# team_throttle_control_draft_2.net
KiCad netlist of a schematic drawn in EAGLE
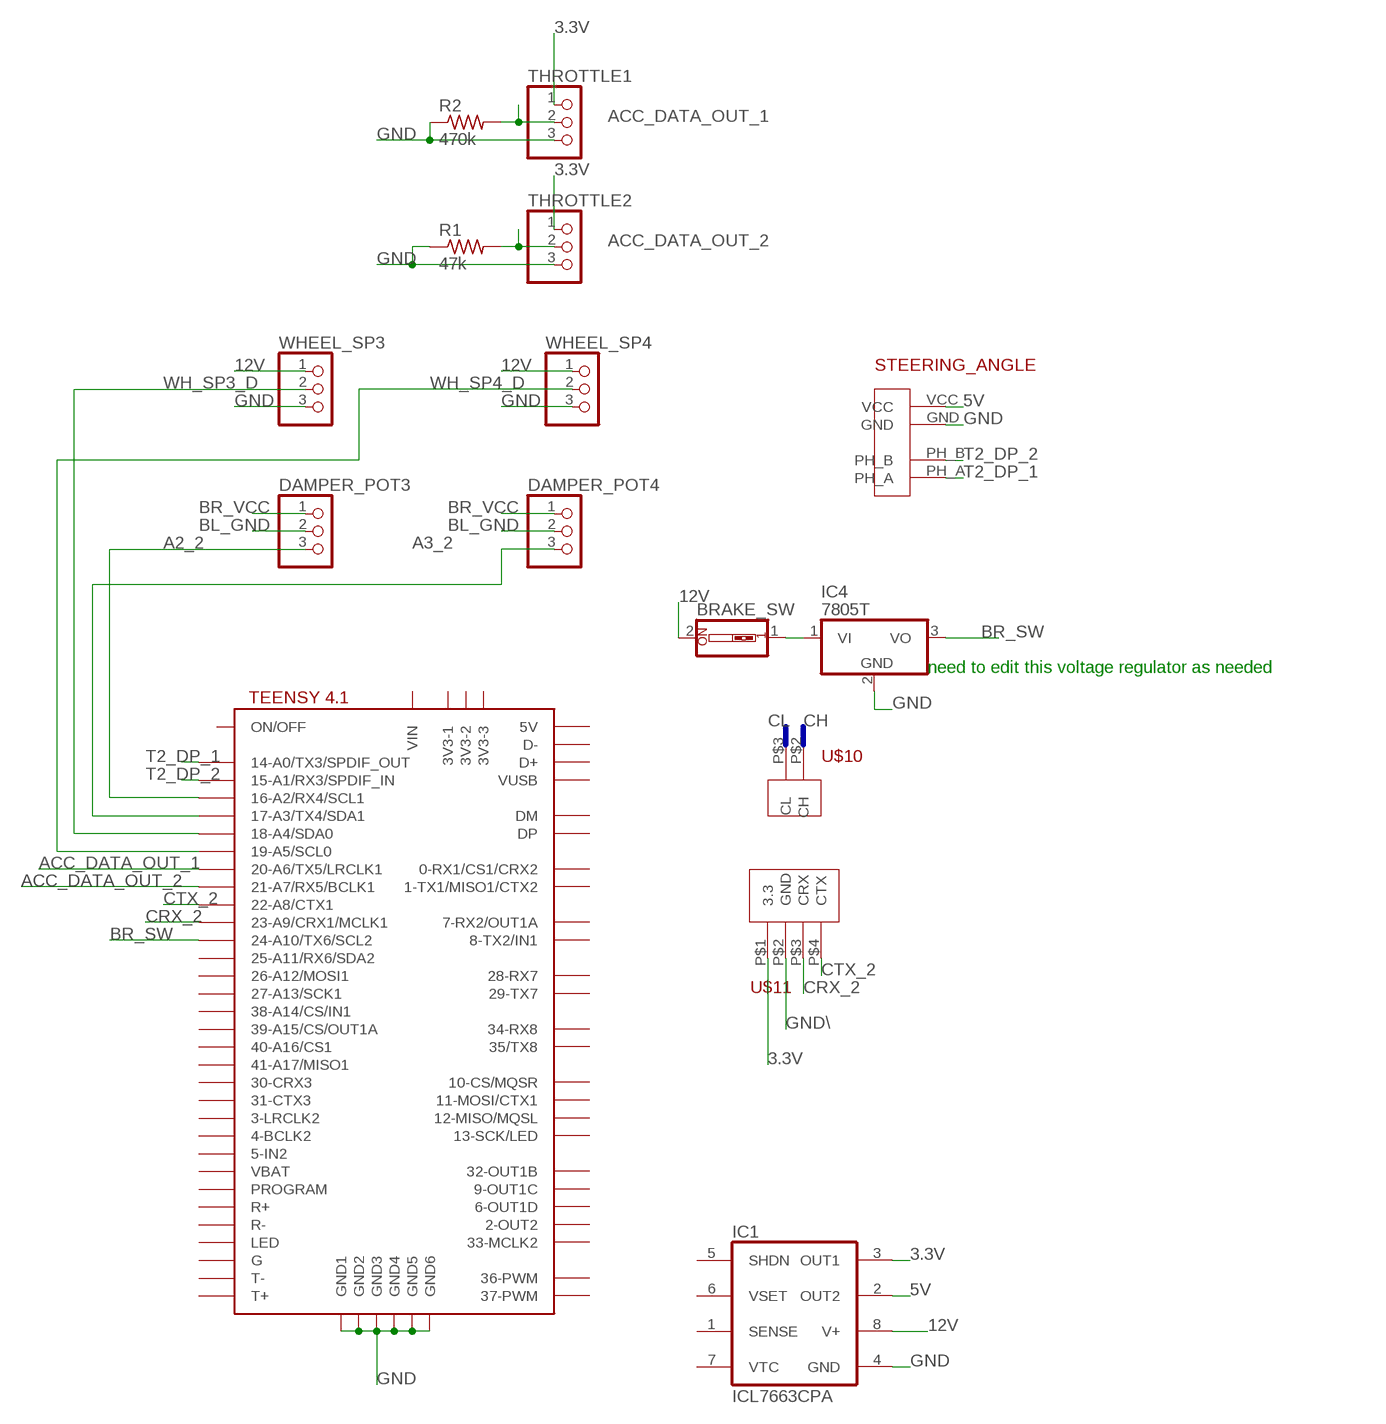
[diagram p0: schematic, sheet 1]

(export (version "E")
  (design (tool "Eeschema 10.0.6"))
  (components
    (comp (ref "BRAKE_SW")
      (value "SW_DIP-1")
      (footprint "eagle-import:EDG-01")
      (libsource (lib "eagle-import") (part "SW_DIP-1"))
    )
    (comp (ref "DAMPER_POT3")
      (value "PINHD-1X3CB")
      (footprint "eagle-import:1X03-CLEANBIG")
      (libsource (lib "eagle-import") (part "PINHD-1X3CB"))
    )
    (comp (ref "DAMPER_POT4")
      (value "PINHD-1X3CB")
      (footprint "eagle-import:1X03-CLEANBIG")
      (libsource (lib "eagle-import") (part "PINHD-1X3CB"))
    )
    (comp (ref "IC1")
      (value "ICL7663CPA")
      (footprint "eagle-import:DIL08")
      (libsource (lib "eagle-import") (part "ICL7663CPA"))
    )
    (comp (ref "IC4")
      (value "7805T")
      (footprint "eagle-import:TO220H")
      (libsource (lib "eagle-import") (part "78T05"))
    )
    (comp (ref "R1")
      (value "47k")
      (footprint "eagle-import:0204_7")
      (libsource (lib "eagle-import") (part "R-US_0204/7"))
    )
    (comp (ref "R2")
      (value "470k")
      (footprint "eagle-import:0204_7")
      (libsource (lib "eagle-import") (part "R-US_0204/7"))
    )
    (comp (ref "STEERING_ANGLE")
      (value "ROTARY_ENCODER")
      (footprint "eagle-import:ROTARY_ENCODER")
      (libsource (lib "eagle-import") (part "ROTARY_ENCODER"))
    )
    (comp (ref "THROTTLE1")
      (value "PINHD-1X3")
      (footprint "eagle-import:1X03")
      (libsource (lib "eagle-import") (part "PINHD-1X3"))
    )
    (comp (ref "THROTTLE2")
      (value "PINHD-1X3")
      (footprint "eagle-import:1X03")
      (libsource (lib "eagle-import") (part "PINHD-1X3"))
    )
    (comp (ref "U$3")
      (value "TEENSY41")
      (footprint "eagle-import:TEENSY41")
      (libsource (lib "eagle-import") (part "TEENSY41"))
    )
    (comp (ref "U$10")
      (value "CAN_BUS")
      (footprint "eagle-import:CAN_BUS")
      (libsource (lib "eagle-import") (part "CAN_BUS"))
    )
    (comp (ref "U$11")
      (value "CAN_TEE")
      (footprint "eagle-import:CAN_TEN")
      (libsource (lib "eagle-import") (part "CAN_TEE"))
    )
    (comp (ref "WHEEL_SP3")
      (value "PINHD-1X3")
      (footprint "eagle-import:1X03")
      (libsource (lib "eagle-import") (part "PINHD-1X3"))
    )
    (comp (ref "WHEEL_SP4")
      (value "PINHD-1X3")
      (footprint "eagle-import:1X03")
      (libsource (lib "eagle-import") (part "PINHD-1X3"))
    )
  )
  (nets
    (net (code "3") (name "/3.3V") (class "Default")
      (node (ref "IC1") (pin "3") (pinfunction "OUT1_3") (pintype "output"))
      (node (ref "THROTTLE1") (pin "1") (pinfunction "1_1") (pintype "passive"))
      (node (ref "THROTTLE2") (pin "1") (pinfunction "1_1") (pintype "passive"))
      (node (ref "U$11") (pin "P$1") (pinfunction "3.3_P$1") (pintype "bidirectional"))
    )
    (net (code "4") (name "/5V") (class "Default")
      (node (ref "IC1") (pin "2") (pinfunction "OUT2_2") (pintype "output"))
      (node (ref "STEERING_ANGLE") (pin "VCC") (pinfunction "VCC_VCC") (pintype "bidirectional"))
    )
    (net (code "5") (name "/12V") (class "Default")
      (node (ref "BRAKE_SW") (pin "2") (pinfunction "2_2") (pintype "passive"))
      (node (ref "IC1") (pin "8") (pinfunction "V+_8") (pintype "power_in"))
      (node (ref "WHEEL_SP3") (pin "1") (pinfunction "1_1") (pintype "passive"))
      (node (ref "WHEEL_SP4") (pin "1") (pinfunction "1_1") (pintype "passive"))
    )
    (net (code "6") (name "/A2_2") (class "Default")
      (node (ref "DAMPER_POT3") (pin "3") (pinfunction "3_3") (pintype "passive"))
      (node (ref "U$3") (pin "16-A2/RX4/SCL1") (pinfunction "16-A2/RX4/SCL1_16-A2/RX4/SCL1") (pintype "bidirectional"))
    )
    (net (code "7") (name "/A3_2") (class "Default")
      (node (ref "DAMPER_POT4") (pin "3") (pinfunction "3_3") (pintype "passive"))
      (node (ref "U$3") (pin "17-A3/TX4/SDA1") (pinfunction "17-A3/TX4/SDA1_17-A3/TX4/SDA1") (pintype "bidirectional"))
    )
    (net (code "8") (name "/ACC_DATA_OUT_1") (class "Default")
      (node (ref "R2") (pin "2") (pinfunction "2_2") (pintype "passive"))
      (node (ref "THROTTLE1") (pin "2") (pinfunction "2_2") (pintype "passive"))
      (node (ref "U$3") (pin "20-A6/TX5/LRCLK1") (pinfunction "20-A6/TX5/LRCLK1_20-A6/TX5/LRCLK1") (pintype "bidirectional"))
    )
    (net (code "9") (name "/ACC_DATA_OUT_2") (class "Default")
      (node (ref "R1") (pin "2") (pinfunction "2_2") (pintype "passive"))
      (node (ref "THROTTLE2") (pin "2") (pinfunction "2_2") (pintype "passive"))
      (node (ref "U$3") (pin "21-A7/RX5/BCLK1") (pinfunction "21-A7/RX5/BCLK1_21-A7/RX5/BCLK1") (pintype "bidirectional"))
    )
    (net (code "10") (name "/BL_GND") (class "Default")
      (node (ref "DAMPER_POT3") (pin "2") (pinfunction "2_2") (pintype "passive"))
      (node (ref "DAMPER_POT4") (pin "2") (pinfunction "2_2") (pintype "passive"))
    )
    (net (code "11") (name "/BR_SW") (class "Default")
      (node (ref "IC4") (pin "3") (pinfunction "VO_3") (pintype "passive"))
      (node (ref "U$3") (pin "24-A10/TX6/SCL2") (pinfunction "24-A10/TX6/SCL2_24-A10/TX6/SCL2") (pintype "bidirectional"))
    )
    (net (code "12") (name "/BR_VCC") (class "Default")
      (node (ref "DAMPER_POT3") (pin "1") (pinfunction "1_1") (pintype "passive"))
      (node (ref "DAMPER_POT4") (pin "1") (pinfunction "1_1") (pintype "passive"))
    )
    (net (code "13") (name "/CRX_2") (class "Default")
      (node (ref "U$11") (pin "P$3") (pinfunction "CRX_P$3") (pintype "bidirectional"))
      (node (ref "U$3") (pin "23-A9/CRX1/MCLK1") (pinfunction "23-A9/CRX1/MCLK1_23-A9/CRX1/MCLK1") (pintype "bidirectional"))
    )
    (net (code "14") (name "/CTX_2") (class "Default")
      (node (ref "U$11") (pin "P$4") (pinfunction "CTX_P$4") (pintype "bidirectional"))
      (node (ref "U$3") (pin "22-A8/CTX1") (pinfunction "22-A8/CTX1_22-A8/CTX1") (pintype "bidirectional"))
    )
    (net (code "15") (name "/GND") (class "Default")
      (node (ref "IC1") (pin "4") (pinfunction "GND_4") (pintype "power_in"))
      (node (ref "IC4") (pin "2") (pinfunction "GND_2") (pintype "passive"))
      (node (ref "R1") (pin "1") (pinfunction "1_1") (pintype "passive"))
      (node (ref "R2") (pin "1") (pinfunction "1_1") (pintype "passive"))
      (node (ref "STEERING_ANGLE") (pin "GND") (pinfunction "GND_GND") (pintype "bidirectional"))
      (node (ref "THROTTLE1") (pin "3") (pinfunction "3_3") (pintype "passive"))
      (node (ref "THROTTLE2") (pin "3") (pinfunction "3_3") (pintype "passive"))
      (node (ref "U$3") (pin "GND1") (pinfunction "GND1_GND1") (pintype "bidirectional"))
      (node (ref "U$3") (pin "GND2") (pinfunction "GND2_GND2") (pintype "bidirectional"))
      (node (ref "U$3") (pin "GND3") (pinfunction "GND3_GND3") (pintype "bidirectional"))
      (node (ref "U$3") (pin "GND4") (pinfunction "GND4_GND4") (pintype "bidirectional"))
      (node (ref "U$3") (pin "GND5") (pinfunction "GND5_GND5") (pintype "bidirectional"))
      (node (ref "U$3") (pin "GND6") (pinfunction "GND6_GND6") (pintype "bidirectional"))
      (node (ref "WHEEL_SP3") (pin "3") (pinfunction "3_3") (pintype "passive"))
      (node (ref "WHEEL_SP4") (pin "3") (pinfunction "3_3") (pintype "passive"))
    )
    (net (code "16") (name "/GND\\") (class "Default")
      (node (ref "U$11") (pin "P$2") (pinfunction "GND_P$2") (pintype "bidirectional"))
    )
    (net (code "17") (name "/T2_DP_1") (class "Default")
      (node (ref "STEERING_ANGLE") (pin "PH_A") (pinfunction "PH_A_PH_A") (pintype "bidirectional"))
      (node (ref "U$3") (pin "14-A0/TX3/SPDIF_OUT") (pinfunction "14-A0/TX3/SPDIF_OUT_14-A0/TX3/SPDIF_OUT") (pintype "bidirectional"))
    )
    (net (code "18") (name "/T2_DP_2") (class "Default")
      (node (ref "STEERING_ANGLE") (pin "PH_B") (pinfunction "PH_B_PH_B") (pintype "bidirectional"))
      (node (ref "U$3") (pin "15-A1/RX3/SPDIF_IN") (pinfunction "15-A1/RX3/SPDIF_IN_15-A1/RX3/SPDIF_IN") (pintype "bidirectional"))
    )
    (net (code "19") (name "/WH_SP3_D") (class "Default")
      (node (ref "U$3") (pin "18-A4/SDA0") (pinfunction "18-A4/SDA0_18-A4/SDA0") (pintype "bidirectional"))
      (node (ref "WHEEL_SP3") (pin "2") (pinfunction "2_2") (pintype "passive"))
    )
    (net (code "20") (name "/WH_SP4_D") (class "Default")
      (node (ref "U$3") (pin "19-A5/SCL0") (pinfunction "19-A5/SCL0_19-A5/SCL0") (pintype "bidirectional"))
      (node (ref "WHEEL_SP4") (pin "2") (pinfunction "2_2") (pintype "passive"))
    )
    (net (code "21") (name "/{CH}") (class "Default")
      (node (ref "U$10") (pin "P$2") (pinfunction "CH_P$2") (pintype "bidirectional"))
    )
    (net (code "22") (name "/{CL}") (class "Default")
      (node (ref "U$10") (pin "P$3") (pinfunction "CL_P$3") (pintype "bidirectional"))
    )
    (net (code "23") (name "Net-(IC4-VI)") (class "Default")
      (node (ref "BRAKE_SW") (pin "1") (pinfunction "1_1") (pintype "passive"))
      (node (ref "IC4") (pin "1") (pinfunction "VI_1") (pintype "input"))
    )
    (net (code "24") (name "unconnected-(IC1-SENSE-Pad1)") (class "Default")
      (node (ref "IC1") (pin "1") (pinfunction "SENSE_1") (pintype "input"))
    )
    (net (code "25") (name "unconnected-(IC1-SHDN-Pad5)") (class "Default")
      (node (ref "IC1") (pin "5") (pinfunction "SHDN_5") (pintype "input"))
    )
    (net (code "26") (name "unconnected-(IC1-VSET-Pad6)") (class "Default")
      (node (ref "IC1") (pin "6") (pinfunction "VSET_6") (pintype "input"))
    )
    (net (code "27") (name "unconnected-(IC1-VTC-Pad7)") (class "Default")
      (node (ref "IC1") (pin "7") (pinfunction "VTC_7") (pintype "passive"))
    )
    (net (code "28") (name "unconnected-(U$3-5V-Pad+5V)") (class "Default")
      (node (ref "U$3") (pin "+5V") (pinfunction "5V_+5V") (pintype "bidirectional"))
    )
    (net (code "29") (name "unconnected-(U$3-8-TX2{slash}IN1-Pad8-TX2{slash}IN2)") (class "Default")
      (node (ref "U$3") (pin "8-TX2/IN2") (pinfunction "8-TX2/IN1_8-TX2/IN2") (pintype "bidirectional"))
    )
    (net (code "30") (name "unconnected-(U$3-10-CS{slash}MQSR-Pad10-CS\\MQSR)") (class "Default")
      (node (ref "U$3") (pin "10-CS\\MQSR") (pinfunction "10-CS/MQSR_10-CS\\MQSR") (pintype "bidirectional"))
    )
    (net (code "31") (name "unconnected-(U$3-35{slash}TX8-Pad35-TX8)") (class "Default")
      (node (ref "U$3") (pin "35-TX8") (pinfunction "35/TX8_35-TX8") (pintype "bidirectional"))
    )
    (net (code "32") (name "unconnected-(U$3-Pad0-RX1{slash}CS1{slash}CRX2)") (class "Default")
      (node (ref "U$3") (pin "0-RX1/CS1/CRX2") (pinfunction "0-RX1/CS1/CRX2_0-RX1/CS1/CRX2") (pintype "bidirectional"))
    )
    (net (code "33") (name "unconnected-(U$3-Pad1-TX1{slash}MISO1{slash}CTX2)") (class "Default")
      (node (ref "U$3") (pin "1-TX1/MISO1/CTX2") (pinfunction "1-TX1/MISO1/CTX2_1-TX1/MISO1/CTX2") (pintype "bidirectional"))
    )
    (net (code "34") (name "unconnected-(U$3-Pad2-OUT2)") (class "Default")
      (node (ref "U$3") (pin "2-OUT2") (pinfunction "2-OUT2_2-OUT2") (pintype "bidirectional"))
    )
    (net (code "35") (name "unconnected-(U$3-Pad3-LRCLK2)") (class "Default")
      (node (ref "U$3") (pin "3-LRCLK2") (pinfunction "3-LRCLK2_3-LRCLK2") (pintype "bidirectional"))
    )
    (net (code "36") (name "unconnected-(U$3-Pad3V3-1)") (class "Default")
      (node (ref "U$3") (pin "3V3-1") (pinfunction "3V3-1_3V3-1") (pintype "bidirectional"))
    )
    (net (code "37") (name "unconnected-(U$3-Pad3V3-2)") (class "Default")
      (node (ref "U$3") (pin "3V3-2") (pinfunction "3V3-2_3V3-2") (pintype "bidirectional"))
    )
    (net (code "38") (name "unconnected-(U$3-Pad3V3-3)") (class "Default")
      (node (ref "U$3") (pin "3V3-3") (pinfunction "3V3-3_3V3-3") (pintype "bidirectional"))
    )
    (net (code "39") (name "unconnected-(U$3-Pad4-BCLK2)") (class "Default")
      (node (ref "U$3") (pin "4-BCLK2") (pinfunction "4-BCLK2_4-BCLK2") (pintype "bidirectional"))
    )
    (net (code "40") (name "unconnected-(U$3-Pad5-IN2)") (class "Default")
      (node (ref "U$3") (pin "5-IN2") (pinfunction "5-IN2_5-IN2") (pintype "bidirectional"))
    )
    (net (code "41") (name "unconnected-(U$3-Pad6-OUT1D)") (class "Default")
      (node (ref "U$3") (pin "6-OUT1D") (pinfunction "6-OUT1D_6-OUT1D") (pintype "bidirectional"))
    )
    (net (code "42") (name "unconnected-(U$3-Pad7-RX2{slash}OUT1A)") (class "Default")
      (node (ref "U$3") (pin "7-RX2/OUT1A") (pinfunction "7-RX2/OUT1A_7-RX2/OUT1A") (pintype "bidirectional"))
    )
    (net (code "43") (name "unconnected-(U$3-Pad9-OUT1C)") (class "Default")
      (node (ref "U$3") (pin "9-OUT1C") (pinfunction "9-OUT1C_9-OUT1C") (pintype "bidirectional"))
    )
    (net (code "44") (name "unconnected-(U$3-Pad11-MOSI{slash}CTX1)") (class "Default")
      (node (ref "U$3") (pin "11-MOSI/CTX1") (pinfunction "11-MOSI/CTX1_11-MOSI/CTX1") (pintype "bidirectional"))
    )
    (net (code "45") (name "unconnected-(U$3-Pad12-MISO{slash}MQSL)") (class "Default")
      (node (ref "U$3") (pin "12-MISO/MQSL") (pinfunction "12-MISO/MQSL_12-MISO/MQSL") (pintype "bidirectional"))
    )
    (net (code "46") (name "unconnected-(U$3-Pad13-SCK{slash}LED)") (class "Default")
      (node (ref "U$3") (pin "13-SCK/LED") (pinfunction "13-SCK/LED_13-SCK/LED") (pintype "bidirectional"))
    )
    (net (code "47") (name "unconnected-(U$3-Pad25-A11{slash}RX6{slash}SDA2)") (class "Default")
      (node (ref "U$3") (pin "25-A11/RX6/SDA2") (pinfunction "25-A11/RX6/SDA2_25-A11/RX6/SDA2") (pintype "bidirectional"))
    )
    (net (code "48") (name "unconnected-(U$3-Pad26-A12{slash}MOSI1)") (class "Default")
      (node (ref "U$3") (pin "26-A12/MOSI1") (pinfunction "26-A12/MOSI1_26-A12/MOSI1") (pintype "bidirectional"))
    )
    (net (code "49") (name "unconnected-(U$3-Pad27-A13{slash}SCK1)") (class "Default")
      (node (ref "U$3") (pin "27-A13/SCK1") (pinfunction "27-A13/SCK1_27-A13/SCK1") (pintype "bidirectional"))
    )
    (net (code "50") (name "unconnected-(U$3-Pad28-RX7)") (class "Default")
      (node (ref "U$3") (pin "28-RX7") (pinfunction "28-RX7_28-RX7") (pintype "bidirectional"))
    )
    (net (code "51") (name "unconnected-(U$3-Pad29-TX7)") (class "Default")
      (node (ref "U$3") (pin "29-TX7") (pinfunction "29-TX7_29-TX7") (pintype "bidirectional"))
    )
    (net (code "52") (name "unconnected-(U$3-Pad30-CRX3)") (class "Default")
      (node (ref "U$3") (pin "30-CRX3") (pinfunction "30-CRX3_30-CRX3") (pintype "bidirectional"))
    )
    (net (code "53") (name "unconnected-(U$3-Pad31-CTX3)") (class "Default")
      (node (ref "U$3") (pin "31-CTX3") (pinfunction "31-CTX3_31-CTX3") (pintype "bidirectional"))
    )
    (net (code "54") (name "unconnected-(U$3-Pad32-OUT1B)") (class "Default")
      (node (ref "U$3") (pin "32-OUT1B") (pinfunction "32-OUT1B_32-OUT1B") (pintype "bidirectional"))
    )
    (net (code "55") (name "unconnected-(U$3-Pad33-MCLK2)") (class "Default")
      (node (ref "U$3") (pin "33-MCLK2") (pinfunction "33-MCLK2_33-MCLK2") (pintype "bidirectional"))
    )
    (net (code "56") (name "unconnected-(U$3-Pad34-RX8)") (class "Default")
      (node (ref "U$3") (pin "34-RX8") (pinfunction "34-RX8_34-RX8") (pintype "bidirectional"))
    )
    (net (code "57") (name "unconnected-(U$3-Pad36-PWM)") (class "Default")
      (node (ref "U$3") (pin "36-PWM") (pinfunction "36-PWM_36-PWM") (pintype "bidirectional"))
    )
    (net (code "58") (name "unconnected-(U$3-Pad37-PWM)") (class "Default")
      (node (ref "U$3") (pin "37-PWM") (pinfunction "37-PWM_37-PWM") (pintype "bidirectional"))
    )
    (net (code "59") (name "unconnected-(U$3-Pad38-A14{slash}CS{slash}IN1)") (class "Default")
      (node (ref "U$3") (pin "38-A14/CS/IN1") (pinfunction "38-A14/CS/IN1_38-A14/CS/IN1") (pintype "bidirectional"))
    )
    (net (code "60") (name "unconnected-(U$3-Pad39-A15{slash}CS{slash}OUT1A)") (class "Default")
      (node (ref "U$3") (pin "39-A15/CS/OUT1A") (pinfunction "39-A15/CS/OUT1A_39-A15/CS/OUT1A") (pintype "bidirectional"))
    )
    (net (code "61") (name "unconnected-(U$3-Pad40-A16{slash}CS1)") (class "Default")
      (node (ref "U$3") (pin "40-A16/CS1") (pinfunction "40-A16/CS1_40-A16/CS1") (pintype "bidirectional"))
    )
    (net (code "62") (name "unconnected-(U$3-Pad41-A17{slash}MISO1)") (class "Default")
      (node (ref "U$3") (pin "41-A17/MISO1") (pinfunction "41-A17/MISO1_41-A17/MISO1") (pintype "bidirectional"))
    )
    (net (code "63") (name "unconnected-(U$3-PadD+)") (class "Default")
      (node (ref "U$3") (pin "D+") (pinfunction "D+_D+") (pintype "bidirectional"))
    )
    (net (code "64") (name "unconnected-(U$3-PadD-)") (class "Default")
      (node (ref "U$3") (pin "D-") (pinfunction "D-_D-") (pintype "bidirectional"))
    )
    (net (code "65") (name "unconnected-(U$3-PadDM)") (class "Default")
      (node (ref "U$3") (pin "DM") (pinfunction "DM_DM") (pintype "bidirectional"))
    )
    (net (code "66") (name "unconnected-(U$3-PadDP)") (class "Default")
      (node (ref "U$3") (pin "DP") (pinfunction "DP_DP") (pintype "bidirectional"))
    )
    (net (code "67") (name "unconnected-(U$3-PadG)") (class "Default")
      (node (ref "U$3") (pin "G") (pinfunction "G_G") (pintype "bidirectional"))
    )
    (net (code "68") (name "unconnected-(U$3-PadLED)") (class "Default")
      (node (ref "U$3") (pin "LED") (pinfunction "LED_LED") (pintype "bidirectional"))
    )
    (net (code "69") (name "unconnected-(U$3-PadON{slash}OFF)") (class "Default")
      (node (ref "U$3") (pin "ON/OFF") (pinfunction "ON/OFF_ON/OFF") (pintype "bidirectional"))
    )
    (net (code "70") (name "unconnected-(U$3-PadPROGRAM)") (class "Default")
      (node (ref "U$3") (pin "PROGRAM") (pinfunction "PROGRAM_PROGRAM") (pintype "bidirectional"))
    )
    (net (code "71") (name "unconnected-(U$3-PadR+)") (class "Default")
      (node (ref "U$3") (pin "R+") (pinfunction "R+_R+") (pintype "bidirectional"))
    )
    (net (code "72") (name "unconnected-(U$3-PadR-)") (class "Default")
      (node (ref "U$3") (pin "R-") (pinfunction "R-_R-") (pintype "bidirectional"))
    )
    (net (code "73") (name "unconnected-(U$3-PadT+)") (class "Default")
      (node (ref "U$3") (pin "T+") (pinfunction "T+_T+") (pintype "bidirectional"))
    )
    (net (code "74") (name "unconnected-(U$3-PadT-)") (class "Default")
      (node (ref "U$3") (pin "T-") (pinfunction "T-_T-") (pintype "bidirectional"))
    )
    (net (code "75") (name "unconnected-(U$3-PadVBAT)") (class "Default")
      (node (ref "U$3") (pin "VBAT") (pinfunction "VBAT_VBAT") (pintype "bidirectional"))
    )
    (net (code "76") (name "unconnected-(U$3-PadVIN)") (class "Default")
      (node (ref "U$3") (pin "VIN") (pinfunction "VIN_VIN") (pintype "bidirectional"))
    )
    (net (code "77") (name "unconnected-(U$3-PadVUSB)") (class "Default")
      (node (ref "U$3") (pin "VUSB") (pinfunction "VUSB_VUSB") (pintype "bidirectional"))
    )
  )
)
